# power_manage.net
KiCad netlist of a schematic drawn in Altium Designer
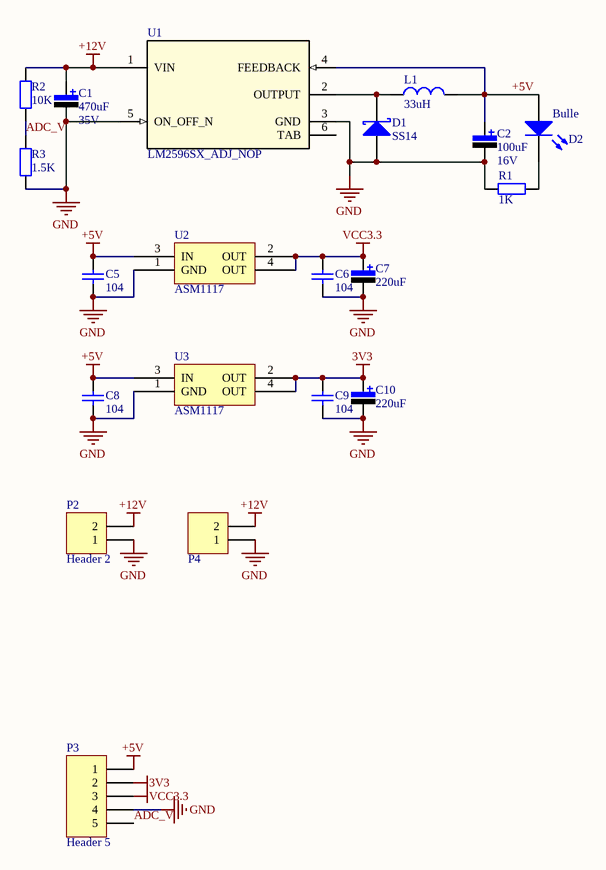
[diagram p0: power_manage.SchDoc]

(export (version "E")
  (design (tool "Eeschema 10.0.6"))
  (components
    (comp (ref "C1")
      (value "470uF")
      (footprint "Fszhang:C-RB-S10")
      (description "极性电解电容")
      (fields
        (field (name "VOL") "35V")
        (field (name "Comment") "Cap Pol")
        (field (name "PUBLISHER") "Altium Limited")
      )
      (libsource (lib "Fszhang") (part "Cap Pol"))
    )
    (comp (ref "C2")
      (value "100uF")
      (footprint "C-RB-S10")
      (description "极性电解电容")
      (fields
        (field (name "VOL") "16V")
        (field (name "Comment") "Cap Pol")
        (field (name "PUBLISHER") "Altium Limited")
      )
      (libsource (lib "Fszhang") (part "Cap Pol"))
    )
    (comp (ref "C5")
      (value "104")
      (footprint "C-RAD-0603")
      (description "无极性电容")
      (fields (field (name "Comment") "Cap") (field (name "PUBLISHER") "Altium Limited"))
      (libsource (lib "Fszhang") (part "Cap"))
    )
    (comp (ref "C6")
      (value "104")
      (footprint "C-RAD-0603")
      (description "无极性电容")
      (fields (field (name "Comment") "Cap") (field (name "PUBLISHER") "Altium Limited"))
      (libsource (lib "Fszhang") (part "Cap"))
    )
    (comp (ref "C7")
      (value "220uF")
      (footprint "C-RB-S8")
      (description "极性电解电容")
      (fields (field (name "Comment") "Cap Pol") (field (name "PUBLISHER") "Altium Limited"))
      (libsource (lib "Fszhang") (part "Cap Pol"))
    )
    (comp (ref "C8")
      (value "104")
      (footprint "C-RAD-0603")
      (description "无极性电容")
      (fields (field (name "Comment") "Cap") (field (name "PUBLISHER") "Altium Limited"))
      (libsource (lib "Fszhang") (part "Cap"))
    )
    (comp (ref "C9")
      (value "104")
      (footprint "C-RAD-0603")
      (description "无极性电容")
      (fields (field (name "Comment") "Cap") (field (name "PUBLISHER") "Altium Limited"))
      (libsource (lib "Fszhang") (part "Cap"))
    )
    (comp (ref "C10")
      (value "220uF")
      (footprint "C-RB-S8")
      (description "极性电解电容")
      (fields (field (name "Comment") "Cap Pol") (field (name "PUBLISHER") "Altium Limited"))
      (libsource (lib "Fszhang") (part "Cap Pol"))
    )
    (comp (ref "D1")
      (value "D-Schottky")
      (footprint "DIODE-SMC")
      (description "肖特基二极管")
      (fields (field (name "TYPE") "SS14") (field (name "PUBLISHER") "Altium Limited"))
      (libsource (lib "Fszhang") (part "D-Schottky"))
    )
    (comp (ref "D2")
      (value "Bulle")
      (footprint "LED_0805")
      (description "发光二极管")
      (fields (field (name "PUBLISHER") "Altium Limited"))
      (libsource (lib "Fszhang") (part "LED0"))
    )
    (comp (ref "L1")
      (value "33uH")
      (footprint "L-SMD-7")
      (description "电感")
      (fields (field (name "Comment") "Inductor") (field (name "PUBLISHER") "Altium Limited"))
      (libsource (lib "Fszhang") (part "Inductor"))
    )
    (comp (ref "P2")
      (value "Header 2")
      (footprint "HDR2X1_B2")
      (description "Header, 2-Pin")
      (fields (field (name "PUBLISHER") "Altium Limited"))
      (libsource (lib "Miscellaneous Connectors") (part "Header 2"))
    )
    (comp (ref "P3")
      (value "Header 5")
      (footprint "HDR1X5")
      (description "Header, 5-Pin")
      (fields (field (name "PUBLISHER") "Altium Limited"))
      (libsource (lib "Miscellaneous Connectors") (part "Header 5"))
    )
    (comp (ref "P4")
      (value "Header 2")
      (footprint "KF301:KF301_2")
      (description "接插件")
      (fields (field (name "PUBLISHER") "Altium Limited"))
      (libsource (lib "Fszhang") (part "Header 2"))
    )
    (comp (ref "R1")
      (value "1K")
      (footprint "0805-1")
      (description "贴片电阻")
      (fields (field (name "Comment") "Res1") (field (name "PUBLISHER") "Altium Limited"))
      (libsource (lib "") (part "Res1_1"))
    )
    (comp (ref "R2")
      (value "10K")
      (footprint "0805-1")
      (description "贴片电阻")
      (fields (field (name "Comment") "Res1") (field (name "PUBLISHER") "Altium Limited"))
      (libsource (lib "Fszhang") (part "Res1"))
    )
    (comp (ref "R3")
      (value "1.5K")
      (footprint "0805-1")
      (description "贴片电阻")
      (fields (field (name "Comment") "Res1") (field (name "PUBLISHER") "Altium Limited"))
      (libsource (lib "Fszhang") (part "Res1"))
    )
    (comp (ref "U1")
      (value "LM2596SX_ADJ_NOP")
      (footprint "TO-263-5")
      (description "Imported")
      (fields
        (field (name "PARTNUMBER") "LM2596SX-ADJ/NOPB")
        (field (name "ALTERNATE_PARTNUMBER") "LM2596S-ADJ/NOPB")
      )
      (libsource (lib "2017-08-02_14-45-44") (part "LM2596SX_ADJ_NOP"))
    )
    (comp (ref "U2")
      (value "ASM1117")
      (footprint "SOT-223")
      (description "3.3V稳压芯片")
      (libsource (lib "Fszhang") (part "ASM1117"))
    )
    (comp (ref "U3")
      (value "ASM1117")
      (footprint "SOT-223")
      (description "3.3V稳压芯片")
      (libsource (lib "Fszhang") (part "ASM1117"))
    )
  )
  (nets
    (net (code "1") (name "+5V") (class "Default")
      (node (ref "C2") (pin "1") (pinfunction "1_1") (pintype "passive"))
      (node (ref "C5") (pin "2") (pinfunction "2_2") (pintype "passive"))
      (node (ref "C8") (pin "2") (pinfunction "2_2") (pintype "passive"))
      (node (ref "D2") (pin "1") (pinfunction "A_1") (pintype "passive"))
      (node (ref "L1") (pin "2") (pinfunction "2_2") (pintype "passive"))
      (node (ref "P3") (pin "1") (pinfunction "1_1") (pintype "passive"))
      (node (ref "U1") (pin "4") (pinfunction "FEEDBACK_4") (pintype "input"))
      (node (ref "U2") (pin "3") (pinfunction "IN_3") (pintype "passive"))
      (node (ref "U3") (pin "3") (pinfunction "IN_3") (pintype "passive"))
    )
    (net (code "2") (name "+12V") (class "Default")
      (node (ref "C1") (pin "1") (pinfunction "1_1") (pintype "passive"))
      (node (ref "P2") (pin "2") (pinfunction "2_2") (pintype "passive"))
      (node (ref "P4") (pin "2") (pinfunction "2_2") (pintype "passive"))
      (node (ref "R2") (pin "2") (pinfunction "2_2") (pintype "passive"))
      (node (ref "U1") (pin "1") (pinfunction "VIN_1") (pintype "power_in"))
    )
    (net (code "3") (name "/ADC_V") (class "Default")
      (node (ref "P3") (pin "5") (pinfunction "5_5") (pintype "passive"))
      (node (ref "R2") (pin "1") (pinfunction "1_1") (pintype "passive"))
      (node (ref "R3") (pin "2") (pinfunction "2_2") (pintype "passive"))
    )
    (net (code "4") (name "3V3") (class "Default")
      (node (ref "C10") (pin "1") (pinfunction "1_1") (pintype "passive"))
      (node (ref "C9") (pin "2") (pinfunction "2_2") (pintype "passive"))
      (node (ref "P3") (pin "2") (pinfunction "2_2") (pintype "passive"))
      (node (ref "U3") (pin "2") (pinfunction "OUT_2") (pintype "passive"))
      (node (ref "U3") (pin "4") (pinfunction "OUT_4") (pintype "passive"))
    )
    (net (code "5") (name "GND") (class "Default")
      (node (ref "C1") (pin "2") (pinfunction "2_2") (pintype "passive"))
      (node (ref "C10") (pin "2") (pinfunction "2_2") (pintype "passive"))
      (node (ref "C2") (pin "2") (pinfunction "2_2") (pintype "passive"))
      (node (ref "C5") (pin "1") (pinfunction "1_1") (pintype "passive"))
      (node (ref "C6") (pin "1") (pinfunction "1_1") (pintype "passive"))
      (node (ref "C7") (pin "2") (pinfunction "2_2") (pintype "passive"))
      (node (ref "C8") (pin "1") (pinfunction "1_1") (pintype "passive"))
      (node (ref "C9") (pin "1") (pinfunction "1_1") (pintype "passive"))
      (node (ref "D1") (pin "1") (pinfunction "A_1") (pintype "passive"))
      (node (ref "P2") (pin "1") (pinfunction "1_1") (pintype "passive"))
      (node (ref "P3") (pin "4") (pinfunction "4_4") (pintype "passive"))
      (node (ref "P4") (pin "1") (pinfunction "1_1") (pintype "passive"))
      (node (ref "R1") (pin "1") (pinfunction "1_1") (pintype "passive"))
      (node (ref "R3") (pin "1") (pinfunction "1_1") (pintype "passive"))
      (node (ref "U1") (pin "3") (pinfunction "GND_3") (pintype "power_in"))
      (node (ref "U1") (pin "5") (pinfunction "ON_OFF_N_5") (pintype "input"))
      (node (ref "U2") (pin "1") (pinfunction "GND_1") (pintype "passive"))
      (node (ref "U3") (pin "1") (pinfunction "GND_1") (pintype "passive"))
    )
    (net (code "6") (name "Net-(D1-K)") (class "Default")
      (node (ref "D1") (pin "2") (pinfunction "K_2") (pintype "passive"))
      (node (ref "L1") (pin "1") (pinfunction "1_1") (pintype "passive"))
      (node (ref "U1") (pin "2") (pinfunction "OUTPUT_2") (pintype "power_in"))
    )
    (net (code "7") (name "Net-(D2-K)") (class "Default")
      (node (ref "D2") (pin "2") (pinfunction "K_2") (pintype "passive"))
      (node (ref "R1") (pin "2") (pinfunction "2_2") (pintype "passive"))
    )
    (net (code "8") (name "VCC3.3") (class "Default")
      (node (ref "C6") (pin "2") (pinfunction "2_2") (pintype "passive"))
      (node (ref "C7") (pin "1") (pinfunction "1_1") (pintype "passive"))
      (node (ref "P3") (pin "3") (pinfunction "3_3") (pintype "passive"))
      (node (ref "U2") (pin "2") (pinfunction "OUT_2") (pintype "passive"))
      (node (ref "U2") (pin "4") (pinfunction "OUT_4") (pintype "passive"))
    )
    (net (code "9") (name "unconnected-(U1-TAB-Pad6)") (class "Default")
      (node (ref "U1") (pin "6") (pinfunction "TAB_6") (pintype "power_in"))
    )
  )
)
